# Level_Shifter.net
KiCad netlist of a schematic drawn in Altium Designer
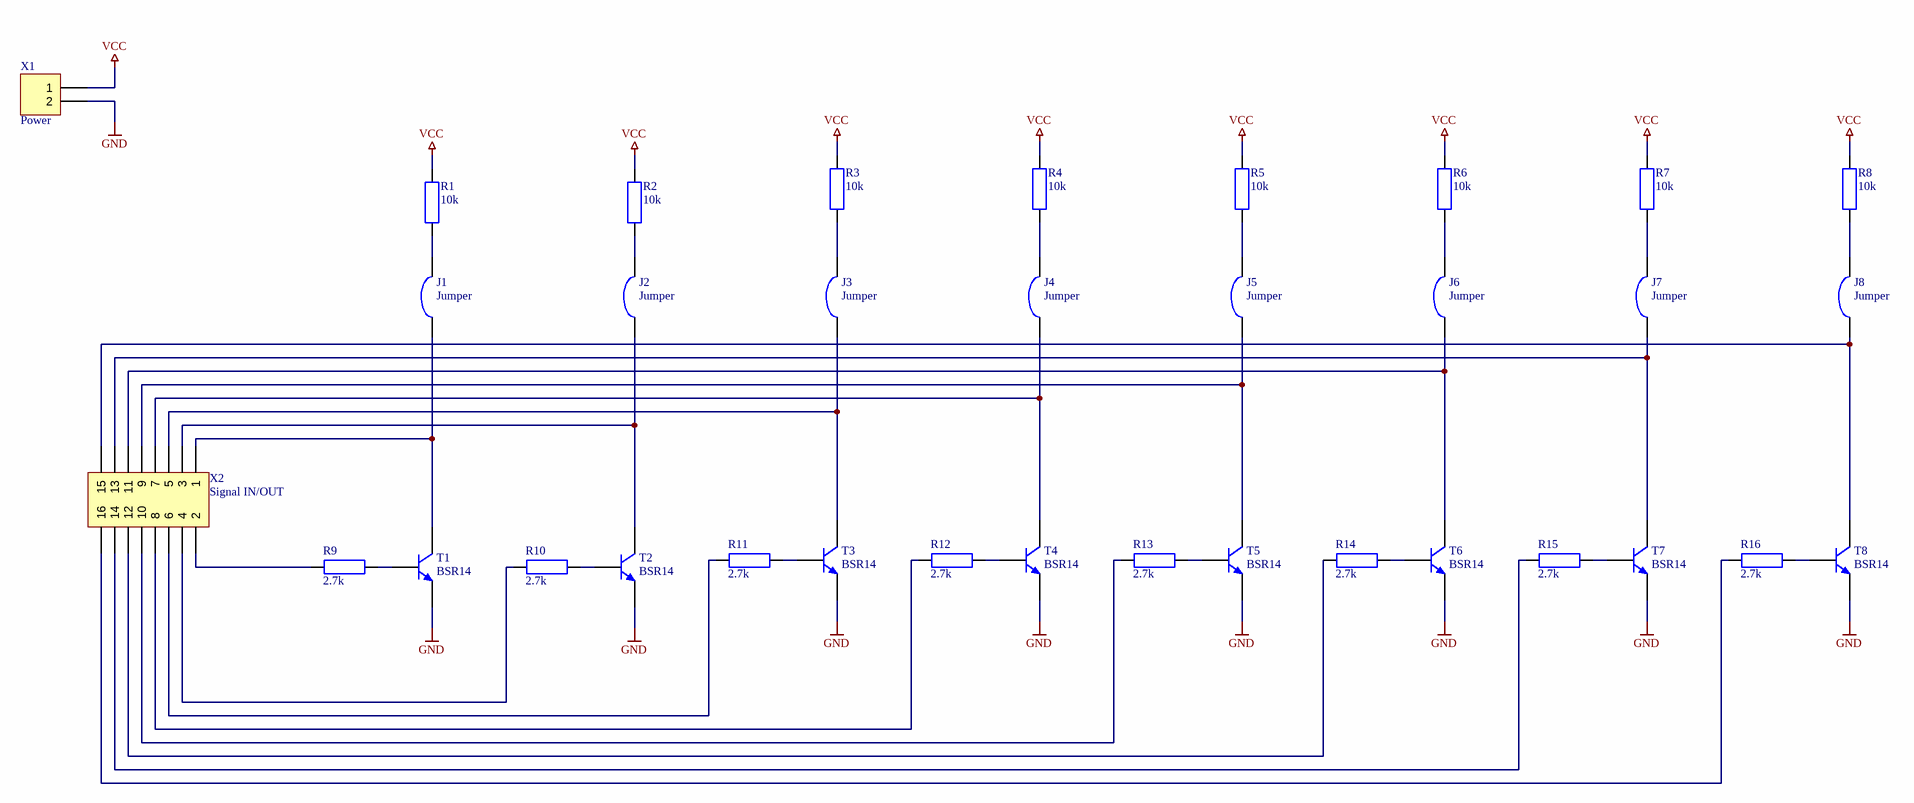
[diagram p0: Level_Shifter.SchDoc]

(export (version "E")
  (design (tool "Eeschema 10.0.6"))
  (components
    (comp (ref "J1")
      (value "Jumper")
      (footprint "Jumper")
      (description "Wire link")
      (libsource (lib "Level_shifter") (part "Jumper"))
    )
    (comp (ref "J2")
      (value "Jumper")
      (footprint "Jumper")
      (description "Wire link")
      (libsource (lib "Level_shifter") (part "Jumper"))
    )
    (comp (ref "J3")
      (value "Jumper")
      (footprint "Jumper")
      (description "Wire link")
      (libsource (lib "Level_shifter") (part "Jumper"))
    )
    (comp (ref "J4")
      (value "Jumper")
      (footprint "Jumper")
      (description "Wire link")
      (libsource (lib "Level_shifter") (part "Jumper"))
    )
    (comp (ref "J5")
      (value "Jumper")
      (footprint "Jumper")
      (description "Wire link")
      (libsource (lib "Level_shifter") (part "Jumper"))
    )
    (comp (ref "J6")
      (value "Jumper")
      (footprint "Jumper")
      (description "Wire link")
      (libsource (lib "Level_shifter") (part "Jumper"))
    )
    (comp (ref "J7")
      (value "Jumper")
      (footprint "Jumper")
      (description "Wire link")
      (libsource (lib "Level_shifter") (part "Jumper"))
    )
    (comp (ref "J8")
      (value "Jumper")
      (footprint "Jumper")
      (description "Wire link")
      (libsource (lib "Level_shifter") (part "Jumper"))
    )
    (comp (ref "R1")
      (value "10k")
      (footprint "0805")
      (description "Normaler Widerstand")
      (libsource (lib "DEVICE_HSLU") (part "R?"))
    )
    (comp (ref "R2")
      (value "10k")
      (footprint "0805")
      (description "Normaler Widerstand")
      (libsource (lib "DEVICE_HSLU") (part "R?"))
    )
    (comp (ref "R3")
      (value "10k")
      (footprint "0805")
      (description "Normaler Widerstand")
      (libsource (lib "DEVICE_HSLU") (part "R?"))
    )
    (comp (ref "R4")
      (value "10k")
      (footprint "0805")
      (description "Normaler Widerstand")
      (libsource (lib "DEVICE_HSLU") (part "R?"))
    )
    (comp (ref "R5")
      (value "10k")
      (footprint "0805")
      (description "Normaler Widerstand")
      (libsource (lib "DEVICE_HSLU") (part "R?"))
    )
    (comp (ref "R6")
      (value "10k")
      (footprint "0805")
      (description "Normaler Widerstand")
      (libsource (lib "DEVICE_HSLU") (part "R?"))
    )
    (comp (ref "R7")
      (value "10k")
      (footprint "0805")
      (description "Normaler Widerstand")
      (libsource (lib "DEVICE_HSLU") (part "R?"))
    )
    (comp (ref "R8")
      (value "10k")
      (footprint "0805")
      (description "Normaler Widerstand")
      (libsource (lib "DEVICE_HSLU") (part "R?"))
    )
    (comp (ref "R9")
      (value "2.7k")
      (footprint "0805")
      (description "Normaler Widerstand")
      (libsource (lib "DEVICE_HSLU") (part "R?"))
    )
    (comp (ref "R10")
      (value "2.7k")
      (footprint "0805")
      (description "Normaler Widerstand")
      (libsource (lib "DEVICE_HSLU") (part "R?"))
    )
    (comp (ref "R11")
      (value "2.7k")
      (footprint "0805")
      (description "Normaler Widerstand")
      (libsource (lib "DEVICE_HSLU") (part "R?"))
    )
    (comp (ref "R12")
      (value "2.7k")
      (footprint "0805")
      (description "Normaler Widerstand")
      (libsource (lib "DEVICE_HSLU") (part "R?"))
    )
    (comp (ref "R13")
      (value "2.7k")
      (footprint "0805")
      (description "Normaler Widerstand")
      (libsource (lib "DEVICE_HSLU") (part "R?"))
    )
    (comp (ref "R14")
      (value "2.7k")
      (footprint "0805")
      (description "Normaler Widerstand")
      (libsource (lib "DEVICE_HSLU") (part "R?"))
    )
    (comp (ref "R15")
      (value "2.7k")
      (footprint "0805")
      (description "Normaler Widerstand")
      (libsource (lib "DEVICE_HSLU") (part "R?"))
    )
    (comp (ref "R16")
      (value "2.7k")
      (footprint "0805")
      (description "Normaler Widerstand")
      (libsource (lib "DEVICE_HSLU") (part "R?"))
    )
    (comp (ref "T1")
      (value "BSR14")
      (footprint "SOT-23A_M")
      (description "NPN General Purpose Amplifier")
      (fields (field (name "PUBLISHER") "Altium Limited"))
      (libsource (lib "FSC Discrete BJT") (part "BC817-25"))
    )
    (comp (ref "T2")
      (value "BSR14")
      (footprint "SOT-23A_M")
      (description "NPN General Purpose Amplifier")
      (fields (field (name "PUBLISHER") "Altium Limited"))
      (libsource (lib "FSC Discrete BJT") (part "BC817-25"))
    )
    (comp (ref "T3")
      (value "BSR14")
      (footprint "SOT-23A_M")
      (description "NPN General Purpose Amplifier")
      (fields (field (name "PUBLISHER") "Altium Limited"))
      (libsource (lib "FSC Discrete BJT") (part "BC817-25"))
    )
    (comp (ref "T4")
      (value "BSR14")
      (footprint "SOT-23A_M")
      (description "NPN General Purpose Amplifier")
      (fields (field (name "PUBLISHER") "Altium Limited"))
      (libsource (lib "FSC Discrete BJT") (part "BC817-25"))
    )
    (comp (ref "T5")
      (value "BSR14")
      (footprint "SOT-23A_M")
      (description "NPN General Purpose Amplifier")
      (fields (field (name "PUBLISHER") "Altium Limited"))
      (libsource (lib "FSC Discrete BJT") (part "BC817-25"))
    )
    (comp (ref "T6")
      (value "BSR14")
      (footprint "SOT-23A_M")
      (description "NPN General Purpose Amplifier")
      (fields (field (name "PUBLISHER") "Altium Limited"))
      (libsource (lib "FSC Discrete BJT") (part "BC817-25"))
    )
    (comp (ref "T7")
      (value "BSR14")
      (footprint "SOT-23A_M")
      (description "NPN General Purpose Amplifier")
      (fields (field (name "PUBLISHER") "Altium Limited"))
      (libsource (lib "FSC Discrete BJT") (part "BC817-25"))
    )
    (comp (ref "T8")
      (value "BSR14")
      (footprint "SOT-23A_M")
      (description "NPN General Purpose Amplifier")
      (fields (field (name "PUBLISHER") "Altium Limited"))
      (libsource (lib "FSC Discrete BJT") (part "BC817-25"))
    )
    (comp (ref "X1")
      (value "Power")
      (footprint "HDR1X2")
      (description "Header, 2-Pin")
      (fields (field (name "PUBLISHER") "Altium Limited"))
      (libsource (lib "Miscellaneous Connectors") (part "Header 2"))
    )
    (comp (ref "X2")
      (value "Signal IN/OUT")
      (footprint "HDR2X8")
      (description "Header, 8-Pin, Dual row")
      (fields (field (name "PUBLISHER") "Altium Limited"))
      (libsource (lib "Miscellaneous Connectors") (part "Header 8X2"))
    )
  )
  (nets
    (net (code "1") (name "GND") (class "Default")
      (node (ref "T1") (pin "2") (pinfunction "E_2") (pintype "passive"))
      (node (ref "T2") (pin "2") (pinfunction "E_2") (pintype "passive"))
      (node (ref "T3") (pin "2") (pinfunction "E_2") (pintype "passive"))
      (node (ref "T4") (pin "2") (pinfunction "E_2") (pintype "passive"))
      (node (ref "T5") (pin "2") (pinfunction "E_2") (pintype "passive"))
      (node (ref "T6") (pin "2") (pinfunction "E_2") (pintype "passive"))
      (node (ref "T7") (pin "2") (pinfunction "E_2") (pintype "passive"))
      (node (ref "T8") (pin "2") (pinfunction "E_2") (pintype "passive"))
      (node (ref "X1") (pin "2") (pinfunction "2_2") (pintype "passive"))
    )
    (net (code "2") (name "Net-(J1-Pad2)") (class "Default")
      (node (ref "J1") (pin "2") (pinfunction "2_2") (pintype "passive"))
      (node (ref "R1") (pin "1") (pintype "passive"))
    )
    (net (code "3") (name "Net-(J2-Pad2)") (class "Default")
      (node (ref "J2") (pin "2") (pinfunction "2_2") (pintype "passive"))
      (node (ref "R2") (pin "1") (pintype "passive"))
    )
    (net (code "4") (name "Net-(J3-Pad2)") (class "Default")
      (node (ref "J3") (pin "2") (pinfunction "2_2") (pintype "passive"))
      (node (ref "R3") (pin "1") (pintype "passive"))
    )
    (net (code "5") (name "Net-(J4-Pad2)") (class "Default")
      (node (ref "J4") (pin "2") (pinfunction "2_2") (pintype "passive"))
      (node (ref "R4") (pin "1") (pintype "passive"))
    )
    (net (code "6") (name "Net-(J5-Pad2)") (class "Default")
      (node (ref "J5") (pin "2") (pinfunction "2_2") (pintype "passive"))
      (node (ref "R5") (pin "1") (pintype "passive"))
    )
    (net (code "7") (name "Net-(J6-Pad2)") (class "Default")
      (node (ref "J6") (pin "2") (pinfunction "2_2") (pintype "passive"))
      (node (ref "R6") (pin "1") (pintype "passive"))
    )
    (net (code "8") (name "Net-(J7-Pad2)") (class "Default")
      (node (ref "J7") (pin "2") (pinfunction "2_2") (pintype "passive"))
      (node (ref "R7") (pin "1") (pintype "passive"))
    )
    (net (code "9") (name "Net-(J8-Pad2)") (class "Default")
      (node (ref "J8") (pin "2") (pinfunction "2_2") (pintype "passive"))
      (node (ref "R8") (pin "1") (pintype "passive"))
    )
    (net (code "10") (name "Net-(R9-Pad1)") (class "Default")
      (node (ref "R9") (pin "1") (pintype "passive"))
      (node (ref "X2") (pin "2") (pinfunction "2_2") (pintype "passive"))
    )
    (net (code "11") (name "Net-(R10-Pad1)") (class "Default")
      (node (ref "R10") (pin "1") (pintype "passive"))
      (node (ref "X2") (pin "4") (pinfunction "4_4") (pintype "passive"))
    )
    (net (code "12") (name "Net-(R11-Pad1)") (class "Default")
      (node (ref "R11") (pin "1") (pintype "passive"))
      (node (ref "X2") (pin "6") (pinfunction "6_6") (pintype "passive"))
    )
    (net (code "13") (name "Net-(R12-Pad1)") (class "Default")
      (node (ref "R12") (pin "1") (pintype "passive"))
      (node (ref "X2") (pin "8") (pinfunction "8_8") (pintype "passive"))
    )
    (net (code "14") (name "Net-(R13-Pad1)") (class "Default")
      (node (ref "R13") (pin "1") (pintype "passive"))
      (node (ref "X2") (pin "10") (pinfunction "10_10") (pintype "passive"))
    )
    (net (code "15") (name "Net-(R14-Pad1)") (class "Default")
      (node (ref "R14") (pin "1") (pintype "passive"))
      (node (ref "X2") (pin "12") (pinfunction "12_12") (pintype "passive"))
    )
    (net (code "16") (name "Net-(R15-Pad1)") (class "Default")
      (node (ref "R15") (pin "1") (pintype "passive"))
      (node (ref "X2") (pin "14") (pinfunction "14_14") (pintype "passive"))
    )
    (net (code "17") (name "Net-(R16-Pad1)") (class "Default")
      (node (ref "R16") (pin "1") (pintype "passive"))
      (node (ref "X2") (pin "16") (pinfunction "16_16") (pintype "passive"))
    )
    (net (code "18") (name "Net-(T1-B)") (class "Default")
      (node (ref "R9") (pin "2") (pintype "passive"))
      (node (ref "T1") (pin "1") (pinfunction "B_1") (pintype "passive"))
    )
    (net (code "19") (name "Net-(T1-C)") (class "Default")
      (node (ref "J1") (pin "1") (pinfunction "1_1") (pintype "passive"))
      (node (ref "T1") (pin "3") (pinfunction "C_3") (pintype "passive"))
      (node (ref "X2") (pin "1") (pinfunction "1_1") (pintype "passive"))
    )
    (net (code "20") (name "Net-(T2-B)") (class "Default")
      (node (ref "R10") (pin "2") (pintype "passive"))
      (node (ref "T2") (pin "1") (pinfunction "B_1") (pintype "passive"))
    )
    (net (code "21") (name "Net-(T2-C)") (class "Default")
      (node (ref "J2") (pin "1") (pinfunction "1_1") (pintype "passive"))
      (node (ref "T2") (pin "3") (pinfunction "C_3") (pintype "passive"))
      (node (ref "X2") (pin "3") (pinfunction "3_3") (pintype "passive"))
    )
    (net (code "22") (name "Net-(T3-B)") (class "Default")
      (node (ref "R11") (pin "2") (pintype "passive"))
      (node (ref "T3") (pin "1") (pinfunction "B_1") (pintype "passive"))
    )
    (net (code "23") (name "Net-(T3-C)") (class "Default")
      (node (ref "J3") (pin "1") (pinfunction "1_1") (pintype "passive"))
      (node (ref "T3") (pin "3") (pinfunction "C_3") (pintype "passive"))
      (node (ref "X2") (pin "5") (pinfunction "5_5") (pintype "passive"))
    )
    (net (code "24") (name "Net-(T4-B)") (class "Default")
      (node (ref "R12") (pin "2") (pintype "passive"))
      (node (ref "T4") (pin "1") (pinfunction "B_1") (pintype "passive"))
    )
    (net (code "25") (name "Net-(T4-C)") (class "Default")
      (node (ref "J4") (pin "1") (pinfunction "1_1") (pintype "passive"))
      (node (ref "T4") (pin "3") (pinfunction "C_3") (pintype "passive"))
      (node (ref "X2") (pin "7") (pinfunction "7_7") (pintype "passive"))
    )
    (net (code "26") (name "Net-(T5-B)") (class "Default")
      (node (ref "R13") (pin "2") (pintype "passive"))
      (node (ref "T5") (pin "1") (pinfunction "B_1") (pintype "passive"))
    )
    (net (code "27") (name "Net-(T5-C)") (class "Default")
      (node (ref "J5") (pin "1") (pinfunction "1_1") (pintype "passive"))
      (node (ref "T5") (pin "3") (pinfunction "C_3") (pintype "passive"))
      (node (ref "X2") (pin "9") (pinfunction "9_9") (pintype "passive"))
    )
    (net (code "28") (name "Net-(T6-B)") (class "Default")
      (node (ref "R14") (pin "2") (pintype "passive"))
      (node (ref "T6") (pin "1") (pinfunction "B_1") (pintype "passive"))
    )
    (net (code "29") (name "Net-(T6-C)") (class "Default")
      (node (ref "J6") (pin "1") (pinfunction "1_1") (pintype "passive"))
      (node (ref "T6") (pin "3") (pinfunction "C_3") (pintype "passive"))
      (node (ref "X2") (pin "11") (pinfunction "11_11") (pintype "passive"))
    )
    (net (code "30") (name "Net-(T7-B)") (class "Default")
      (node (ref "R15") (pin "2") (pintype "passive"))
      (node (ref "T7") (pin "1") (pinfunction "B_1") (pintype "passive"))
    )
    (net (code "31") (name "Net-(T7-C)") (class "Default")
      (node (ref "J7") (pin "1") (pinfunction "1_1") (pintype "passive"))
      (node (ref "T7") (pin "3") (pinfunction "C_3") (pintype "passive"))
      (node (ref "X2") (pin "13") (pinfunction "13_13") (pintype "passive"))
    )
    (net (code "32") (name "Net-(T8-B)") (class "Default")
      (node (ref "R16") (pin "2") (pintype "passive"))
      (node (ref "T8") (pin "1") (pinfunction "B_1") (pintype "passive"))
    )
    (net (code "33") (name "Net-(T8-C)") (class "Default")
      (node (ref "J8") (pin "1") (pinfunction "1_1") (pintype "passive"))
      (node (ref "T8") (pin "3") (pinfunction "C_3") (pintype "passive"))
      (node (ref "X2") (pin "15") (pinfunction "15_15") (pintype "passive"))
    )
    (net (code "34") (name "VCC") (class "Default")
      (node (ref "R1") (pin "2") (pintype "passive"))
      (node (ref "R2") (pin "2") (pintype "passive"))
      (node (ref "R3") (pin "2") (pintype "passive"))
      (node (ref "R4") (pin "2") (pintype "passive"))
      (node (ref "R5") (pin "2") (pintype "passive"))
      (node (ref "R6") (pin "2") (pintype "passive"))
      (node (ref "R7") (pin "2") (pintype "passive"))
      (node (ref "R8") (pin "2") (pintype "passive"))
      (node (ref "X1") (pin "1") (pinfunction "1_1") (pintype "passive"))
    )
  )
)
